# uMultimeter_OLED_Sch.net
KiCad netlist of a schematic drawn in Altium Designer
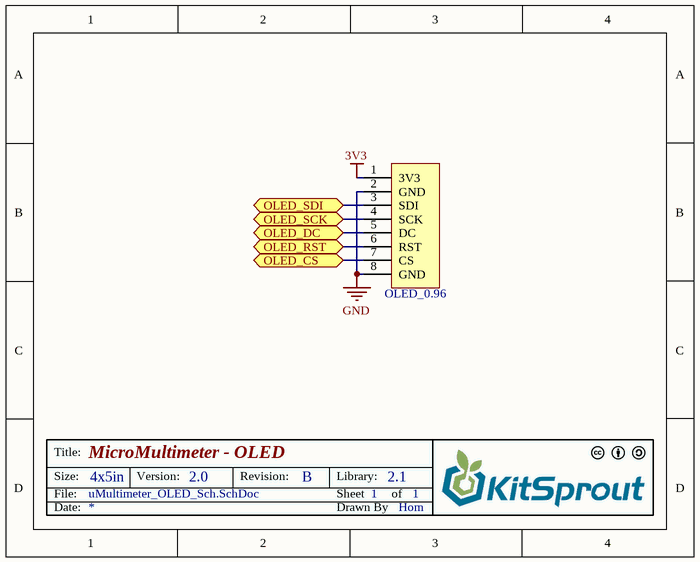
[diagram p0: uMultimeter_OLED_Sch.SchDoc]

(export (version "E")
  (design (tool "Eeschema 10.0.6"))
  (components
    (comp (ref "OLED_0.96")
      (value "OLED_0.96")
      (footprint "PCB_Module:OLED_0.96_96x64_v2")
      (description "Module")
      (libsource (lib "SCH_Module") (part "OLED_0.96_96*64_v2"))
    )
  )
  (nets
    (net (code "1") (name "/OLED_CS") (class "Default")
      (node (ref "OLED_0.96") (pin "7") (pinfunction "CS_7") (pintype "passive"))
    )
    (net (code "2") (name "/OLED_DC") (class "Default")
      (node (ref "OLED_0.96") (pin "5") (pinfunction "DC_5") (pintype "passive"))
    )
    (net (code "3") (name "/OLED_RST") (class "Default")
      (node (ref "OLED_0.96") (pin "6") (pinfunction "RST_6") (pintype "passive"))
    )
    (net (code "4") (name "/OLED_SCK") (class "Default")
      (node (ref "OLED_0.96") (pin "4") (pinfunction "SCK_4") (pintype "passive"))
    )
    (net (code "5") (name "/OLED_SDI") (class "Default")
      (node (ref "OLED_0.96") (pin "3") (pinfunction "SDI_3") (pintype "passive"))
    )
    (net (code "6") (name "3V3") (class "Default")
      (node (ref "OLED_0.96") (pin "1") (pinfunction "3V3_1") (pintype "passive"))
    )
    (net (code "7") (name "GND") (class "Default")
      (node (ref "OLED_0.96") (pin "2") (pinfunction "GND_2") (pintype "passive"))
      (node (ref "OLED_0.96") (pin "8") (pinfunction "GND_8") (pintype "passive"))
    )
  )
)
